# MCU.net
KiCad netlist of a schematic drawn in Altium Designer
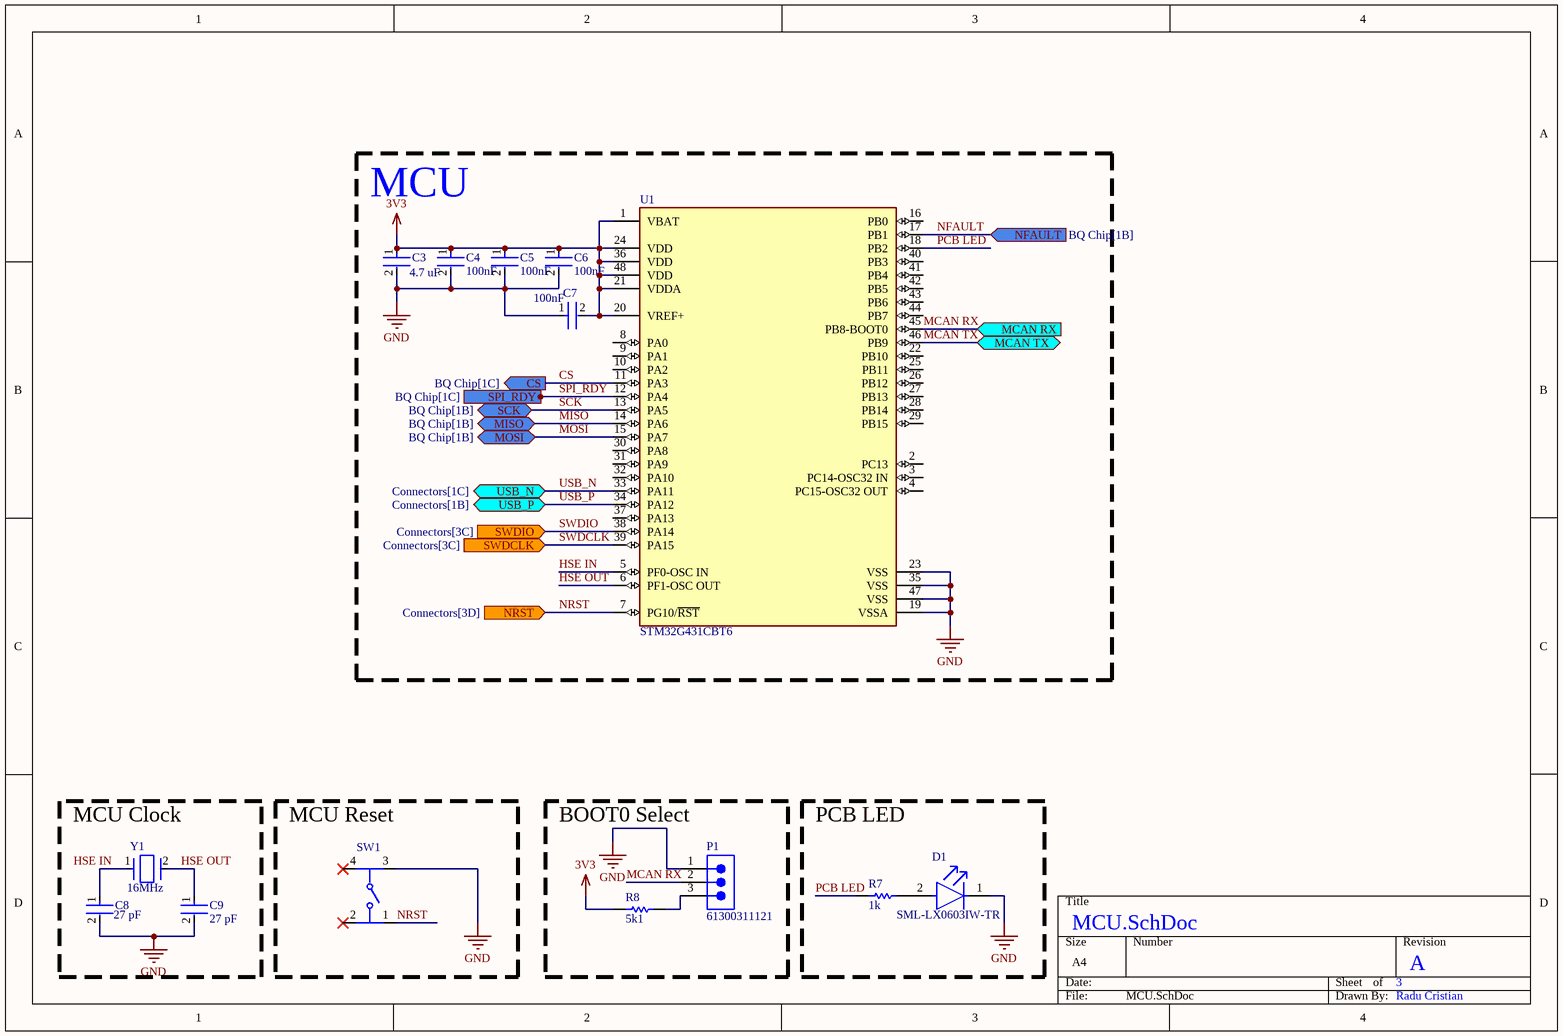
[diagram p0: MCU.SchDoc]

(export (version "E")
  (design (tool "Eeschema 10.0.6"))
  (components
    (comp (ref "C3")
      (value "CC0603KRX5R5BB475")
      (footprint "FP-CC0603-DA-MFG")
      (description "CAP CER 4.7UF 6.3V X5R 0603")
      (fields
        (field (name "TOLERANCE") "0.1")
        (field (name "VOLTAGE") "6.3 V")
        (field (name "CAPACITANCE") "4.7 uF")
      )
      (libsource (lib "Altium Content Vault") (part "11868f565c42a9108669ba33697ecf6"))
    )
    (comp (ref "C4")
      (value "CC0603JRX7R9BB104")
      (footprint "FP-CC0603-DA-IPC_A")
      (description "CAP CER 0.1UF 50V X7R 0603")
      (fields (field (name "CAPACITANCE") "100nF") (field (name "TOLERANCE") "5%"))
      (libsource (lib "Altium Content Vault") (part "02cd4be3c70576c341d710602a673aa"))
    )
    (comp (ref "C5")
      (value "CC0603JRX7R9BB104")
      (footprint "FP-CC0603-DA-IPC_A")
      (description "CAP CER 0.1UF 50V X7R 0603")
      (fields (field (name "CAPACITANCE") "100nF") (field (name "TOLERANCE") "5%"))
      (libsource (lib "Altium Content Vault") (part "02cd4be3c70576c341d710602a673aa"))
    )
    (comp (ref "C6")
      (value "CC0603JRX7R9BB104")
      (footprint "FP-CC0603-DA-IPC_A")
      (description "CAP CER 0.1UF 50V X7R 0603")
      (fields (field (name "CAPACITANCE") "100nF") (field (name "TOLERANCE") "5%"))
      (libsource (lib "Altium Content Vault") (part "02cd4be3c70576c341d710602a673aa"))
    )
    (comp (ref "C7")
      (value "CC0603JRX7R9BB104")
      (footprint "FP-CC0603-DA-IPC_A")
      (description "CAP CER 0.1UF 50V X7R 0603")
      (fields (field (name "CAPACITANCE") "100nF") (field (name "TOLERANCE") "5%"))
      (libsource (lib "Altium Content Vault") (part "02cd4be3c70576c341d710602a673aa"))
    )
    (comp (ref "C8")
      (value "27 pF")
      (footprint "FP-C0603C-CF-MFG")
      (description "CAP CER 27PF 50V C0G/NP0 0603")
      (fields
        (field (name "TOLERANCE") "0.05")
        (field (name "OCTOPART") "https://octopart.com/c0603c270j5gactu-kemet-136059")
      )
      (libsource (lib "Altium Content Vault") (part "b4654b650e69147ec39a6b967a45e02"))
    )
    (comp (ref "C9")
      (value "27 pF")
      (footprint "FP-C0603C-CF-MFG")
      (description "CAP CER 27PF 50V C0G/NP0 0603")
      (fields
        (field (name "TOLERANCE") "0.05")
        (field (name "OCTOPART") "https://octopart.com/c0603c270j5gactu-kemet-136059")
      )
      (libsource (lib "Altium Content Vault") (part "b4654b650e69147ec39a6b967a45e02"))
    )
    (comp (ref "D1")
      (value "SML-LX0603IW-TR")
      (footprint "FP-SML-LX0603IW-TR-MFG")
      (description "LED RED DIFFUSED SMD")
      (libsource (lib "Altium Content Vault") (part "8706943c75ba83719d021d2fdc84c58"))
    )
    (comp (ref "P1")
      (value "61300311121")
      (footprint "61300311121")
      (libsource (lib "Altium Content Vault") (part "Header_Male_1R_03P"))
    )
    (comp (ref "R7")
      (value "ERJ-6ENF1001V")
      (footprint "RESC2013X70X40ML20T20")
      (description "Chip Resistor, 1 KOhm, +/- 1%, 0.125 W, -55 to 155 degC, 0805 (2012 Metric), RoHS, Tape and Reel")
      (fields (field (name "MANUFACTURER") "Panasonic") (field (name "PARAMETER 1") "1k"))
      (libsource (lib "Altium Content Vault") (part "RES-2"))
    )
    (comp (ref "R8")
      (value "RK73H2ATTD5101F")
      (footprint "RESC2013X60X30NL20T20")
      (fields (field (name "MANUFACTURER") "KOA Speer") (field (name "PARAMETER 1") "5k1"))
      (libsource (lib "Altium Content Vault") (part "RES"))
    )
    (comp (ref "SW1")
      (value "PTS810SJM250SMTRLFS")
      (footprint "FP-PTS810SJM250SMTRLFS-MFG")
      (description "SWITCH TACTILE SPST-NO 0.05A 16V")
      (libsource (lib "Altium Content Vault") (part "1adf0dd01260c80cf25a44bfd6b99ba"))
    )
    (comp (ref "U1")
      (value "STM32G431CBT6")
      (footprint "FP-LQFP48-5B-MFG")
      (description "MAINSTREAM ARM CORTEX-M4+ MCU 17")
      (fields
        (field (name "MANUFACTURER") "STMicroelectronics")
        (field (name "OCTOPART") "https://octopart.com/stm32g431cbt6-stmicroelectronics-98835224")
      )
      (libsource (lib "Altium Content Vault") (part "08b09c1d51ec08ade740842f2b8671b"))
    )
    (comp (ref "Y1")
      (value "ABM3-16.000MHZ-D2Y-T")
      (footprint "FP-ABM3-MFG")
      (description "Crystal 16MHz ±20ppm 18pF SMD-2 5mm x 3.2mm")
      (fields (field (name "TOLERANCE") "20ppm") (field (name "FREQUENCY") "16MHz"))
      (libsource (lib "Altium Content Vault") (part "c23a69dc6c9e2f18f2079038eb95dd1"))
    )
  )
  (nets
    (net (code "1") (name "/CS") (class "Default")
      (node (ref "U1") (pin "11") (pinfunction "PA3_11") (pintype "bidirectional"))
    )
    (net (code "2") (name "/HSE IN") (class "Default")
      (node (ref "C8") (pin "1") (pinfunction "1_1") (pintype "passive"))
      (node (ref "U1") (pin "5") (pinfunction "PF0-OSC_IN_5") (pintype "bidirectional"))
      (node (ref "Y1") (pin "1") (pinfunction "1_1") (pintype "passive"))
    )
    (net (code "3") (name "/HSE OUT") (class "Default")
      (node (ref "C9") (pin "1") (pinfunction "1_1") (pintype "passive"))
      (node (ref "U1") (pin "6") (pinfunction "PF1-OSC_OUT_6") (pintype "bidirectional"))
      (node (ref "Y1") (pin "2") (pinfunction "2_2") (pintype "passive"))
    )
    (net (code "4") (name "/MCAN RX") (class "Default")
      (node (ref "P1") (pin "2") (pinfunction "2_2") (pintype "passive"))
      (node (ref "U1") (pin "45") (pinfunction "PB8-BOOT0_45") (pintype "bidirectional"))
    )
    (net (code "5") (name "/MCAN TX") (class "Default")
      (node (ref "U1") (pin "46") (pinfunction "PB9_46") (pintype "bidirectional"))
    )
    (net (code "6") (name "/MISO") (class "Default")
      (node (ref "U1") (pin "14") (pinfunction "PA6_14") (pintype "bidirectional"))
    )
    (net (code "7") (name "/MOSI") (class "Default")
      (node (ref "U1") (pin "15") (pinfunction "PA7_15") (pintype "bidirectional"))
    )
    (net (code "8") (name "/NFAULT") (class "Default")
      (node (ref "U1") (pin "17") (pinfunction "PB1_17") (pintype "bidirectional"))
    )
    (net (code "9") (name "/NRST") (class "Default")
      (node (ref "SW1") (pin "1") (pinfunction "1_1") (pintype "passive"))
      (node (ref "U1") (pin "7") (pinfunction "PG10/~{RST}_7") (pintype "bidirectional"))
    )
    (net (code "10") (name "/PCB LED") (class "Default")
      (node (ref "R7") (pin "1") (pinfunction "1_1") (pintype "passive"))
      (node (ref "U1") (pin "18") (pinfunction "PB2_18") (pintype "bidirectional"))
    )
    (net (code "11") (name "/SCK") (class "Default")
      (node (ref "U1") (pin "13") (pinfunction "PA5_13") (pintype "bidirectional"))
    )
    (net (code "12") (name "/SPI_RDY") (class "Default")
      (node (ref "U1") (pin "12") (pinfunction "PA4_12") (pintype "bidirectional"))
    )
    (net (code "13") (name "/SWDCLK") (class "Default")
      (node (ref "U1") (pin "39") (pinfunction "PA15_39") (pintype "bidirectional"))
    )
    (net (code "14") (name "/SWDIO") (class "Default")
      (node (ref "U1") (pin "38") (pinfunction "PA14_38") (pintype "bidirectional"))
    )
    (net (code "15") (name "/USB_N") (class "Default")
      (node (ref "U1") (pin "33") (pinfunction "PA11_33") (pintype "bidirectional"))
    )
    (net (code "16") (name "/USB_P") (class "Default")
      (node (ref "U1") (pin "34") (pinfunction "PA12_34") (pintype "bidirectional"))
    )
    (net (code "17") (name "3V3") (class "Default")
      (node (ref "C3") (pin "1") (pinfunction "1_1") (pintype "passive"))
      (node (ref "C4") (pin "1") (pinfunction "1_1") (pintype "passive"))
      (node (ref "C5") (pin "1") (pinfunction "1_1") (pintype "passive"))
      (node (ref "C6") (pin "1") (pinfunction "1_1") (pintype "passive"))
      (node (ref "C7") (pin "2") (pinfunction "2_2") (pintype "passive"))
      (node (ref "R8") (pin "2") (pinfunction "2_2") (pintype "passive"))
      (node (ref "U1") (pin "1") (pinfunction "VBAT_1") (pintype "power_in"))
      (node (ref "U1") (pin "20") (pinfunction "VREF+_20") (pintype "power_in"))
      (node (ref "U1") (pin "21") (pinfunction "VDDA_21") (pintype "power_in"))
      (node (ref "U1") (pin "24") (pinfunction "VDD_24") (pintype "power_in"))
      (node (ref "U1") (pin "36") (pinfunction "VDD_36") (pintype "power_in"))
      (node (ref "U1") (pin "48") (pinfunction "VDD_48") (pintype "power_in"))
    )
    (net (code "18") (name "GND") (class "Default")
      (node (ref "C3") (pin "2") (pinfunction "2_2") (pintype "passive"))
      (node (ref "C4") (pin "2") (pinfunction "2_2") (pintype "passive"))
      (node (ref "C5") (pin "2") (pinfunction "2_2") (pintype "passive"))
      (node (ref "C6") (pin "2") (pinfunction "2_2") (pintype "passive"))
      (node (ref "C7") (pin "1") (pinfunction "1_1") (pintype "passive"))
      (node (ref "C8") (pin "2") (pinfunction "2_2") (pintype "passive"))
      (node (ref "C9") (pin "2") (pinfunction "2_2") (pintype "passive"))
      (node (ref "D1") (pin "1") (pinfunction "C_1") (pintype "passive"))
      (node (ref "P1") (pin "1") (pinfunction "1_1") (pintype "passive"))
      (node (ref "SW1") (pin "3") (pinfunction "3_3") (pintype "passive"))
      (node (ref "U1") (pin "19") (pinfunction "VSSA_19") (pintype "power_in"))
      (node (ref "U1") (pin "23") (pinfunction "VSS_23") (pintype "power_in"))
      (node (ref "U1") (pin "35") (pinfunction "VSS_35") (pintype "power_in"))
      (node (ref "U1") (pin "47") (pinfunction "VSS_47") (pintype "power_in"))
    )
    (net (code "19") (name "Net-(D1-A)") (class "Default")
      (node (ref "D1") (pin "2") (pinfunction "A_2") (pintype "passive"))
      (node (ref "R7") (pin "2") (pinfunction "2_2") (pintype "passive"))
    )
    (net (code "20") (name "Net-(P1-Pad3)") (class "Default")
      (node (ref "P1") (pin "3") (pinfunction "3_3") (pintype "passive"))
      (node (ref "R8") (pin "1") (pinfunction "1_1") (pintype "passive"))
    )
    (net (code "21") (name "unconnected-(SW1-Pad2)") (class "Default")
      (node (ref "SW1") (pin "2") (pinfunction "2_2") (pintype "passive+no_connect"))
    )
    (net (code "22") (name "unconnected-(SW1-Pad4)") (class "Default")
      (node (ref "SW1") (pin "4") (pinfunction "4_4") (pintype "passive+no_connect"))
    )
    (net (code "23") (name "unconnected-(U1-PA0-Pad8)") (class "Default")
      (node (ref "U1") (pin "8") (pinfunction "PA0_8") (pintype "bidirectional"))
    )
    (net (code "24") (name "unconnected-(U1-PA1-Pad9)") (class "Default")
      (node (ref "U1") (pin "9") (pinfunction "PA1_9") (pintype "bidirectional"))
    )
    (net (code "25") (name "unconnected-(U1-PA2-Pad10)") (class "Default")
      (node (ref "U1") (pin "10") (pinfunction "PA2_10") (pintype "bidirectional"))
    )
    (net (code "26") (name "unconnected-(U1-PA8-Pad30)") (class "Default")
      (node (ref "U1") (pin "30") (pinfunction "PA8_30") (pintype "bidirectional"))
    )
    (net (code "27") (name "unconnected-(U1-PA9-Pad31)") (class "Default")
      (node (ref "U1") (pin "31") (pinfunction "PA9_31") (pintype "bidirectional"))
    )
    (net (code "28") (name "unconnected-(U1-PA10-Pad32)") (class "Default")
      (node (ref "U1") (pin "32") (pinfunction "PA10_32") (pintype "bidirectional"))
    )
    (net (code "29") (name "unconnected-(U1-PA13-Pad37)") (class "Default")
      (node (ref "U1") (pin "37") (pinfunction "PA13_37") (pintype "bidirectional"))
    )
    (net (code "30") (name "unconnected-(U1-PB0-Pad16)") (class "Default")
      (node (ref "U1") (pin "16") (pinfunction "PB0_16") (pintype "bidirectional"))
    )
    (net (code "31") (name "unconnected-(U1-PB3-Pad40)") (class "Default")
      (node (ref "U1") (pin "40") (pinfunction "PB3_40") (pintype "bidirectional"))
    )
    (net (code "32") (name "unconnected-(U1-PB4-Pad41)") (class "Default")
      (node (ref "U1") (pin "41") (pinfunction "PB4_41") (pintype "bidirectional"))
    )
    (net (code "33") (name "unconnected-(U1-PB5-Pad42)") (class "Default")
      (node (ref "U1") (pin "42") (pinfunction "PB5_42") (pintype "bidirectional"))
    )
    (net (code "34") (name "unconnected-(U1-PB6-Pad43)") (class "Default")
      (node (ref "U1") (pin "43") (pinfunction "PB6_43") (pintype "bidirectional"))
    )
    (net (code "35") (name "unconnected-(U1-PB7-Pad44)") (class "Default")
      (node (ref "U1") (pin "44") (pinfunction "PB7_44") (pintype "bidirectional"))
    )
    (net (code "36") (name "unconnected-(U1-PB10-Pad22)") (class "Default")
      (node (ref "U1") (pin "22") (pinfunction "PB10_22") (pintype "bidirectional"))
    )
    (net (code "37") (name "unconnected-(U1-PB11-Pad25)") (class "Default")
      (node (ref "U1") (pin "25") (pinfunction "PB11_25") (pintype "bidirectional"))
    )
    (net (code "38") (name "unconnected-(U1-PB12-Pad26)") (class "Default")
      (node (ref "U1") (pin "26") (pinfunction "PB12_26") (pintype "bidirectional"))
    )
    (net (code "39") (name "unconnected-(U1-PB13-Pad27)") (class "Default")
      (node (ref "U1") (pin "27") (pinfunction "PB13_27") (pintype "bidirectional"))
    )
    (net (code "40") (name "unconnected-(U1-PB14-Pad28)") (class "Default")
      (node (ref "U1") (pin "28") (pinfunction "PB14_28") (pintype "bidirectional"))
    )
    (net (code "41") (name "unconnected-(U1-PB15-Pad29)") (class "Default")
      (node (ref "U1") (pin "29") (pinfunction "PB15_29") (pintype "bidirectional"))
    )
    (net (code "42") (name "unconnected-(U1-PC13-Pad2)") (class "Default")
      (node (ref "U1") (pin "2") (pinfunction "PC13_2") (pintype "bidirectional"))
    )
    (net (code "43") (name "unconnected-(U1-PC14-OSC32_IN-Pad3)") (class "Default")
      (node (ref "U1") (pin "3") (pinfunction "PC14-OSC32_IN_3") (pintype "bidirectional"))
    )
    (net (code "44") (name "unconnected-(U1-PC15-OSC32_OUT-Pad4)") (class "Default")
      (node (ref "U1") (pin "4") (pinfunction "PC15-OSC32_OUT_4") (pintype "bidirectional"))
    )
  )
)
